# tick-wifi-mini-mk-1_2.net
KiCad netlist of a schematic drawn in EAGLE
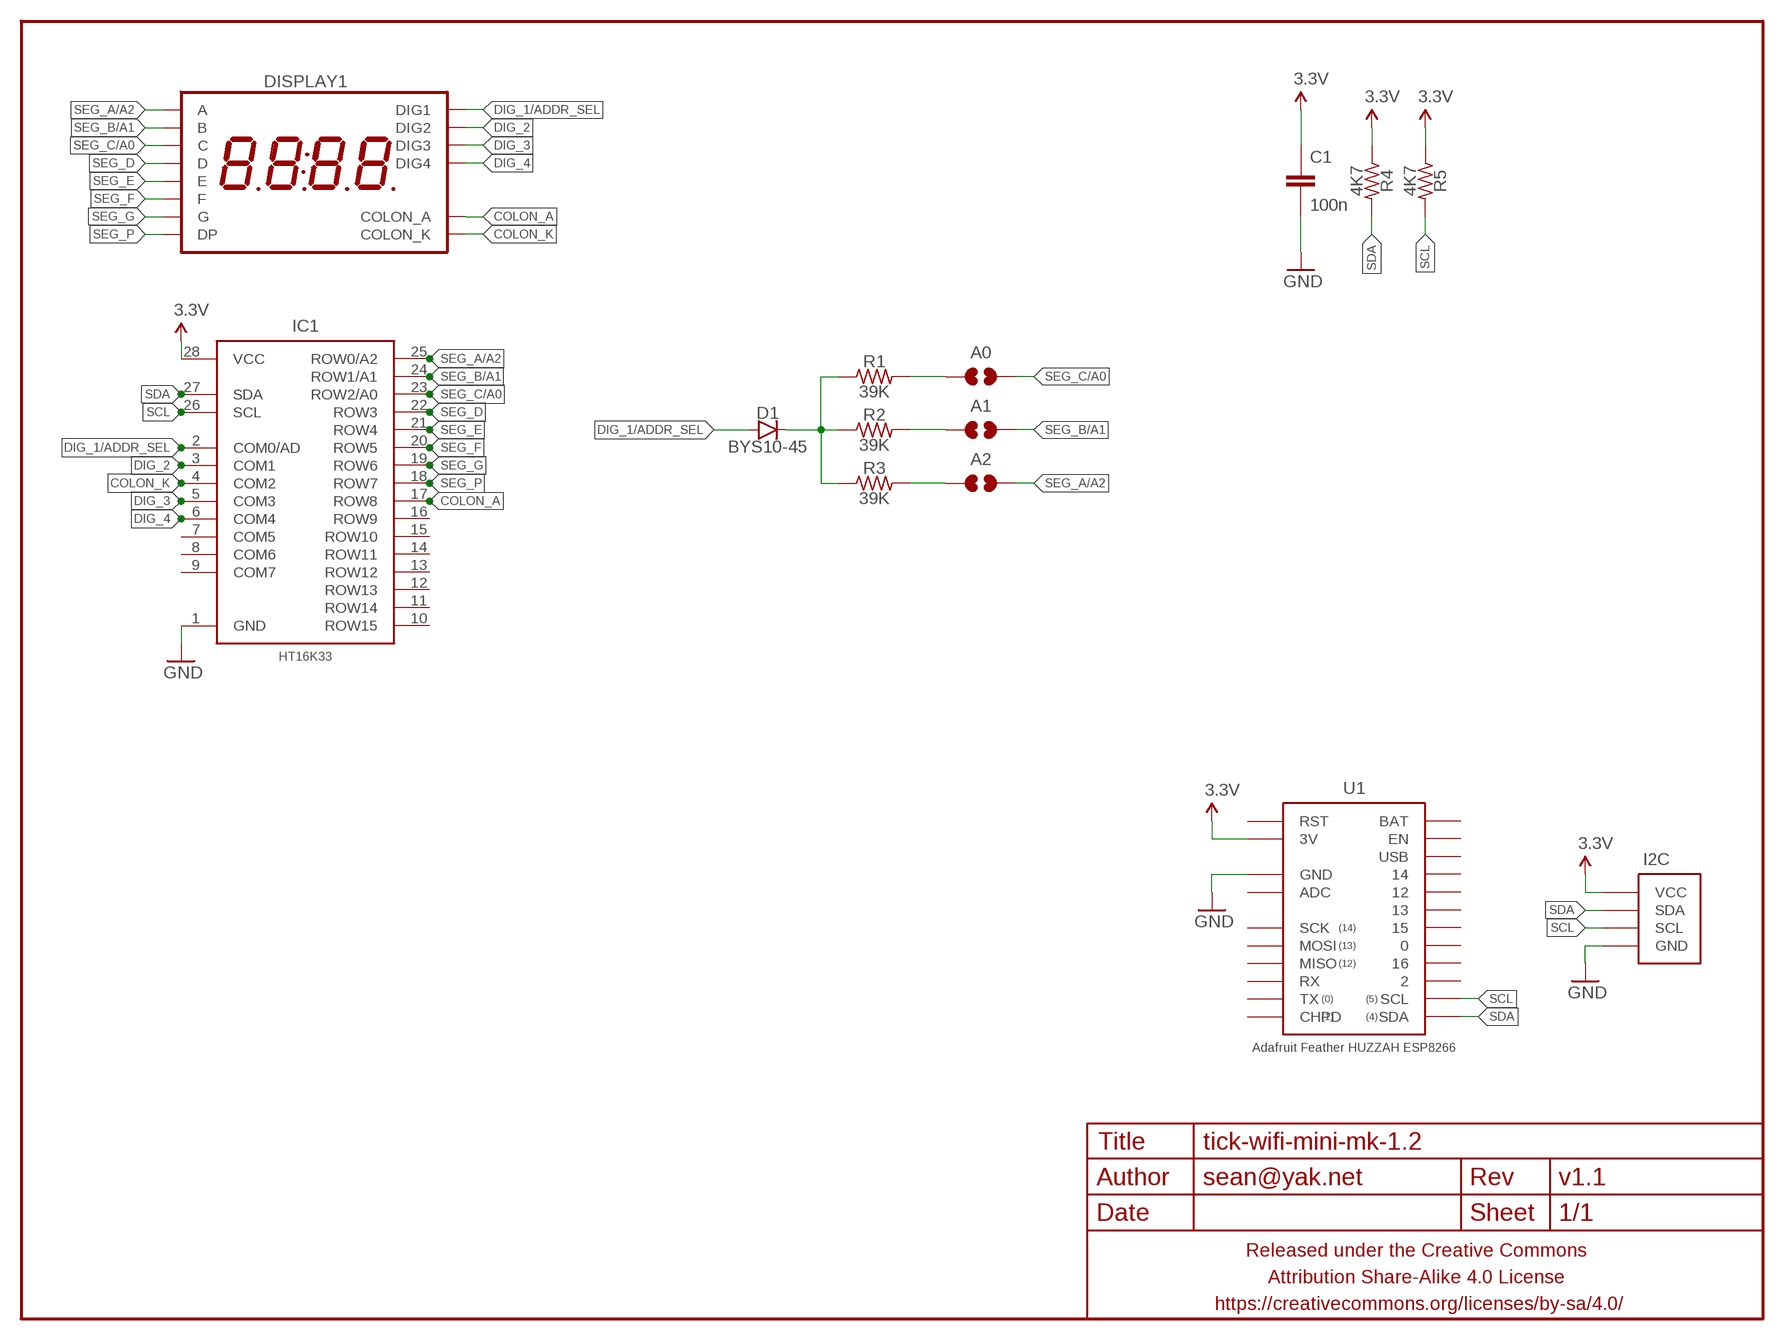
[diagram p0: schematic, sheet 1]

(export (version "E")
  (design (tool "Eeschema 10.0.6"))
  (components
    (comp (ref "A0")
      (value "JUMPER-PAD-2-NOYES_SILK")
      (footprint "eagle-import:PAD-JUMPER-2-NO_YES_SILK")
      (libsource (lib "eagle-import") (part "JUMPER-PAD-2-NOYES_SILK"))
    )
    (comp (ref "A1")
      (value "JUMPER-PAD-2-NOYES_SILK")
      (footprint "eagle-import:PAD-JUMPER-2-NO_YES_SILK")
      (libsource (lib "eagle-import") (part "JUMPER-PAD-2-NOYES_SILK"))
    )
    (comp (ref "A2")
      (value "JUMPER-PAD-2-NOYES_SILK")
      (footprint "eagle-import:PAD-JUMPER-2-NO_YES_SILK")
      (libsource (lib "eagle-import") (part "JUMPER-PAD-2-NOYES_SILK"))
    )
    (comp (ref "C1")
      (value "100n")
      (footprint "eagle-import:C0805")
      (libsource (lib "eagle-import") (part "CAPACITOR-CERAMICC0805"))
    )
    (comp (ref "D1")
      (value "BYS10-45")
      (footprint "eagle-import:SOD123")
      (libsource (lib "eagle-import") (part "DIODESOD123"))
    )
    (comp (ref "DISPLAY1")
      (value "7SEG_4DIGIT_COLON14.2MM-CC")
      (footprint "eagle-import:7SEG_4DIG_0.56IN_14MM_ADAFRUIT")
      (libsource (lib "eagle-import") (part "7SEG_4DIGIT_COLON14.2MM-CC"))
    )
    (comp (ref "FRAME1")
      (value "FRAME-LETTERNO_PACKAGE")
      (footprint "eagle-import:DUMMY")
      (fields (field (name "DESIGNER") "sean@yak.net") (field (name "VERSION") "v1.1"))
      (libsource (lib "eagle-import") (part "FRAME-LETTERNO_PACKAGE"))
    )
    (comp (ref "I2C")
      (value "M04-I2CJST-4-PH-VERT-CENTERED-I2C")
      (footprint "eagle-import:JST-4-PH-VERT-PTH-CENTERED-I2C")
      (libsource (lib "eagle-import") (part "M04-I2CJST-4-PH-VERT-CENTERED-I2C"))
    )
    (comp (ref "IC1")
      (value "HT16K33")
      (footprint "eagle-import:SOIC28W")
      (libsource (lib "eagle-import") (part "HT16K33-28SOIC28W"))
    )
    (comp (ref "R1")
      (value "39K")
      (footprint "eagle-import:R0805")
      (libsource (lib "eagle-import") (part "RESISTORR0805"))
    )
    (comp (ref "R2")
      (value "39K")
      (footprint "eagle-import:R0805")
      (libsource (lib "eagle-import") (part "RESISTORR0805"))
    )
    (comp (ref "R3")
      (value "39K")
      (footprint "eagle-import:R0805")
      (libsource (lib "eagle-import") (part "RESISTORR0805"))
    )
    (comp (ref "R4")
      (value "4K7")
      (footprint "eagle-import:R0805")
      (libsource (lib "eagle-import") (part "RESISTORR0805"))
    )
    (comp (ref "R5")
      (value "4K7")
      (footprint "eagle-import:R0805")
      (libsource (lib "eagle-import") (part "RESISTORR0805"))
    )
    (comp (ref "U1")
      (value "Adafruit Feather HUZZAH ESP8266")
      (footprint "eagle-import:ADAFRUIT_FEATHER_HUZZAH_NOSILK")
      (libsource (lib "eagle-import") (part "ADAFRUIT_FEATHER_HUZZAH_ESP8266NOSILK"))
    )
  )
  (nets
    (net (code "1") (name "3.3V") (class "Default")
      (node (ref "C1") (pin "1") (pinfunction "1_1") (pintype "passive"))
      (node (ref "I2C") (pin "2") (pinfunction "VCC_2") (pintype "bidirectional"))
      (node (ref "IC1") (pin "28") (pinfunction "VCC_28") (pintype "bidirectional"))
      (node (ref "R4") (pin "1") (pinfunction "1_1") (pintype "passive"))
      (node (ref "R5") (pin "1") (pinfunction "1_1") (pintype "passive"))
      (node (ref "U1") (pin "3V") (pinfunction "3V_3V") (pintype "bidirectional"))
    )
    (net (code "2") (name "COLON_A") (class "Default")
      (node (ref "DISPLAY1") (pin "P$8") (pinfunction "COLON_A_P$8") (pintype "passive"))
      (node (ref "IC1") (pin "17") (pinfunction "ROW8_17") (pintype "bidirectional"))
    )
    (net (code "3") (name "COLON_K") (class "Default")
      (node (ref "DISPLAY1") (pin "P$7") (pinfunction "COLON_K_P$7") (pintype "passive"))
      (node (ref "IC1") (pin "4") (pinfunction "COM2_4") (pintype "bidirectional"))
    )
    (net (code "4") (name "DIG_1{slash}ADDR_SEL") (class "Default")
      (node (ref "D1") (pin "A") (pinfunction "A_A") (pintype "passive"))
      (node (ref "DISPLAY1") (pin "P$14") (pinfunction "DIG1_P$14") (pintype "passive"))
      (node (ref "IC1") (pin "2") (pinfunction "COM0/AD_2") (pintype "bidirectional"))
    )
    (net (code "5") (name "DIG_2") (class "Default")
      (node (ref "DISPLAY1") (pin "P$11") (pinfunction "DIG2_P$11") (pintype "passive"))
      (node (ref "IC1") (pin "3") (pinfunction "COM1_3") (pintype "bidirectional"))
    )
    (net (code "6") (name "DIG_3") (class "Default")
      (node (ref "DISPLAY1") (pin "P$10") (pinfunction "DIG3_P$10") (pintype "passive"))
      (node (ref "IC1") (pin "5") (pinfunction "COM3_5") (pintype "bidirectional"))
    )
    (net (code "7") (name "DIG_4") (class "Default")
      (node (ref "DISPLAY1") (pin "P$6") (pinfunction "DIG4_P$6") (pintype "passive"))
      (node (ref "IC1") (pin "6") (pinfunction "COM4_6") (pintype "bidirectional"))
    )
    (net (code "8") (name "GND") (class "Default")
      (node (ref "C1") (pin "2") (pinfunction "2_2") (pintype "passive"))
      (node (ref "I2C") (pin "1") (pinfunction "GND_1") (pintype "bidirectional"))
      (node (ref "IC1") (pin "1") (pinfunction "GND_1") (pintype "bidirectional"))
      (node (ref "U1") (pin "GND@0") (pinfunction "GND_GND@0") (pintype "bidirectional"))
    )
    (net (code "9") (name "Net-(A0-Pad1)") (class "Default")
      (node (ref "A0") (pin "1") (pinfunction "1_1") (pintype "passive"))
      (node (ref "R1") (pin "2") (pinfunction "2_2") (pintype "passive"))
    )
    (net (code "10") (name "Net-(A1-Pad1)") (class "Default")
      (node (ref "A1") (pin "1") (pinfunction "1_1") (pintype "passive"))
      (node (ref "R2") (pin "2") (pinfunction "2_2") (pintype "passive"))
    )
    (net (code "11") (name "Net-(A2-Pad1)") (class "Default")
      (node (ref "A2") (pin "1") (pinfunction "1_1") (pintype "passive"))
      (node (ref "R3") (pin "2") (pinfunction "2_2") (pintype "passive"))
    )
    (net (code "12") (name "Net-(D1-PadC)") (class "Default")
      (node (ref "D1") (pin "C") (pinfunction "C_C") (pintype "passive"))
      (node (ref "R1") (pin "1") (pinfunction "1_1") (pintype "passive"))
      (node (ref "R2") (pin "1") (pinfunction "1_1") (pintype "passive"))
      (node (ref "R3") (pin "1") (pinfunction "1_1") (pintype "passive"))
    )
    (net (code "13") (name "SCL") (class "Default")
      (node (ref "I2C") (pin "4") (pinfunction "SCL_4") (pintype "bidirectional"))
      (node (ref "IC1") (pin "26") (pinfunction "SCL_26") (pintype "bidirectional"))
      (node (ref "R5") (pin "2") (pinfunction "2_2") (pintype "passive"))
      (node (ref "U1") (pin "SCL") (pinfunction "SCL_SCL") (pintype "bidirectional"))
    )
    (net (code "14") (name "SDA") (class "Default")
      (node (ref "I2C") (pin "3") (pinfunction "SDA_3") (pintype "bidirectional"))
      (node (ref "IC1") (pin "27") (pinfunction "SDA_27") (pintype "bidirectional"))
      (node (ref "R4") (pin "2") (pinfunction "2_2") (pintype "passive"))
      (node (ref "U1") (pin "SDA") (pinfunction "SDA_SDA") (pintype "bidirectional"))
    )
    (net (code "15") (name "SEG_A{slash}A2") (class "Default")
      (node (ref "A2") (pin "2") (pinfunction "2_2") (pintype "passive"))
      (node (ref "DISPLAY1") (pin "P$13") (pinfunction "A_P$13") (pintype "passive"))
      (node (ref "IC1") (pin "25") (pinfunction "ROW0/A2_25") (pintype "bidirectional"))
    )
    (net (code "16") (name "SEG_B{slash}A1") (class "Default")
      (node (ref "A1") (pin "2") (pinfunction "2_2") (pintype "passive"))
      (node (ref "DISPLAY1") (pin "P$9") (pinfunction "B_P$9") (pintype "passive"))
      (node (ref "IC1") (pin "24") (pinfunction "ROW1/A1_24") (pintype "bidirectional"))
    )
    (net (code "17") (name "SEG_C{slash}A0") (class "Default")
      (node (ref "A0") (pin "2") (pinfunction "2_2") (pintype "passive"))
      (node (ref "DISPLAY1") (pin "P$4") (pinfunction "C_P$4") (pintype "passive"))
      (node (ref "IC1") (pin "23") (pinfunction "ROW2/A0_23") (pintype "bidirectional"))
    )
    (net (code "18") (name "SEG_D") (class "Default")
      (node (ref "DISPLAY1") (pin "P$2") (pinfunction "D_P$2") (pintype "passive"))
      (node (ref "IC1") (pin "22") (pinfunction "ROW3_22") (pintype "bidirectional"))
    )
    (net (code "19") (name "SEG_E") (class "Default")
      (node (ref "DISPLAY1") (pin "P$1") (pinfunction "E_P$1") (pintype "passive"))
      (node (ref "IC1") (pin "21") (pinfunction "ROW4_21") (pintype "bidirectional"))
    )
    (net (code "20") (name "SEG_F") (class "Default")
      (node (ref "DISPLAY1") (pin "P$12") (pinfunction "F_P$12") (pintype "passive"))
      (node (ref "IC1") (pin "20") (pinfunction "ROW5_20") (pintype "bidirectional"))
    )
    (net (code "21") (name "SEG_G") (class "Default")
      (node (ref "DISPLAY1") (pin "P$5") (pinfunction "G_P$5") (pintype "passive"))
      (node (ref "IC1") (pin "19") (pinfunction "ROW6_19") (pintype "bidirectional"))
    )
    (net (code "22") (name "SEG_P") (class "Default")
      (node (ref "DISPLAY1") (pin "P$3") (pinfunction "DP_P$3") (pintype "passive"))
      (node (ref "IC1") (pin "18") (pinfunction "ROW7_18") (pintype "bidirectional"))
    )
    (net (code "23") (name "unconnected-(IC1-COM5-Pad7)") (class "Default")
      (node (ref "IC1") (pin "7") (pinfunction "COM5_7") (pintype "bidirectional"))
    )
    (net (code "24") (name "unconnected-(IC1-COM6-Pad8)") (class "Default")
      (node (ref "IC1") (pin "8") (pinfunction "COM6_8") (pintype "bidirectional"))
    )
    (net (code "25") (name "unconnected-(IC1-COM7-Pad9)") (class "Default")
      (node (ref "IC1") (pin "9") (pinfunction "COM7_9") (pintype "bidirectional"))
    )
    (net (code "26") (name "unconnected-(IC1-ROW9-Pad16)") (class "Default")
      (node (ref "IC1") (pin "16") (pinfunction "ROW9_16") (pintype "bidirectional"))
    )
    (net (code "27") (name "unconnected-(IC1-ROW10-Pad15)") (class "Default")
      (node (ref "IC1") (pin "15") (pinfunction "ROW10_15") (pintype "bidirectional"))
    )
    (net (code "28") (name "unconnected-(IC1-ROW11-Pad14)") (class "Default")
      (node (ref "IC1") (pin "14") (pinfunction "ROW11_14") (pintype "bidirectional"))
    )
    (net (code "29") (name "unconnected-(IC1-ROW12-Pad13)") (class "Default")
      (node (ref "IC1") (pin "13") (pinfunction "ROW12_13") (pintype "bidirectional"))
    )
    (net (code "30") (name "unconnected-(IC1-ROW13-Pad12)") (class "Default")
      (node (ref "IC1") (pin "12") (pinfunction "ROW13_12") (pintype "bidirectional"))
    )
    (net (code "31") (name "unconnected-(IC1-ROW14-Pad11)") (class "Default")
      (node (ref "IC1") (pin "11") (pinfunction "ROW14_11") (pintype "bidirectional"))
    )
    (net (code "32") (name "unconnected-(IC1-ROW15-Pad10)") (class "Default")
      (node (ref "IC1") (pin "10") (pinfunction "ROW15_10") (pintype "bidirectional"))
    )
    (net (code "33") (name "unconnected-(U1-Pad0)") (class "Default")
      (node (ref "U1") (pin "0") (pinfunction "0_0") (pintype "bidirectional"))
    )
    (net (code "34") (name "unconnected-(U1-Pad2)") (class "Default")
      (node (ref "U1") (pin "2") (pinfunction "2_2") (pintype "bidirectional"))
    )
    (net (code "35") (name "unconnected-(U1-Pad12)") (class "Default")
      (node (ref "U1") (pin "12") (pinfunction "12_12") (pintype "bidirectional"))
    )
    (net (code "36") (name "unconnected-(U1-Pad13)") (class "Default")
      (node (ref "U1") (pin "13") (pinfunction "13_13") (pintype "bidirectional"))
    )
    (net (code "37") (name "unconnected-(U1-Pad14)") (class "Default")
      (node (ref "U1") (pin "14") (pinfunction "14_14") (pintype "bidirectional"))
    )
    (net (code "38") (name "unconnected-(U1-Pad15)") (class "Default")
      (node (ref "U1") (pin "15") (pinfunction "15_15") (pintype "bidirectional"))
    )
    (net (code "39") (name "unconnected-(U1-Pad16)") (class "Default")
      (node (ref "U1") (pin "16") (pinfunction "16_16") (pintype "bidirectional"))
    )
    (net (code "40") (name "unconnected-(U1-PadADC)") (class "Default")
      (node (ref "U1") (pin "ADC") (pinfunction "ADC_ADC") (pintype "bidirectional"))
    )
    (net (code "41") (name "unconnected-(U1-PadBAT)") (class "Default")
      (node (ref "U1") (pin "BAT") (pinfunction "BAT_BAT") (pintype "bidirectional"))
    )
    (net (code "42") (name "unconnected-(U1-PadCHPD)") (class "Default")
      (node (ref "U1") (pin "CHPD") (pinfunction "CHPD_CHPD") (pintype "bidirectional"))
    )
    (net (code "43") (name "unconnected-(U1-PadEN)") (class "Default")
      (node (ref "U1") (pin "EN") (pinfunction "EN_EN") (pintype "bidirectional"))
    )
    (net (code "44") (name "unconnected-(U1-PadMISO)") (class "Default")
      (node (ref "U1") (pin "MISO") (pinfunction "MISO_MISO") (pintype "bidirectional"))
    )
    (net (code "45") (name "unconnected-(U1-PadMOSI)") (class "Default")
      (node (ref "U1") (pin "MOSI") (pinfunction "MOSI_MOSI") (pintype "bidirectional"))
    )
    (net (code "46") (name "unconnected-(U1-PadRST)") (class "Default")
      (node (ref "U1") (pin "RST") (pinfunction "RST_RST") (pintype "bidirectional"))
    )
    (net (code "47") (name "unconnected-(U1-PadRX)") (class "Default")
      (node (ref "U1") (pin "RX") (pinfunction "RX_RX") (pintype "bidirectional"))
    )
    (net (code "48") (name "unconnected-(U1-PadSCK)") (class "Default")
      (node (ref "U1") (pin "SCK") (pinfunction "SCK_SCK") (pintype "bidirectional"))
    )
    (net (code "49") (name "unconnected-(U1-PadTX)") (class "Default")
      (node (ref "U1") (pin "TX") (pinfunction "TX_TX") (pintype "bidirectional"))
    )
    (net (code "50") (name "unconnected-(U1-PadUSB)") (class "Default")
      (node (ref "U1") (pin "USB") (pinfunction "USB_USB") (pintype "bidirectional"))
    )
  )
)
